# Control_Gates.net
KiCad netlist of a schematic drawn in Altium Designer
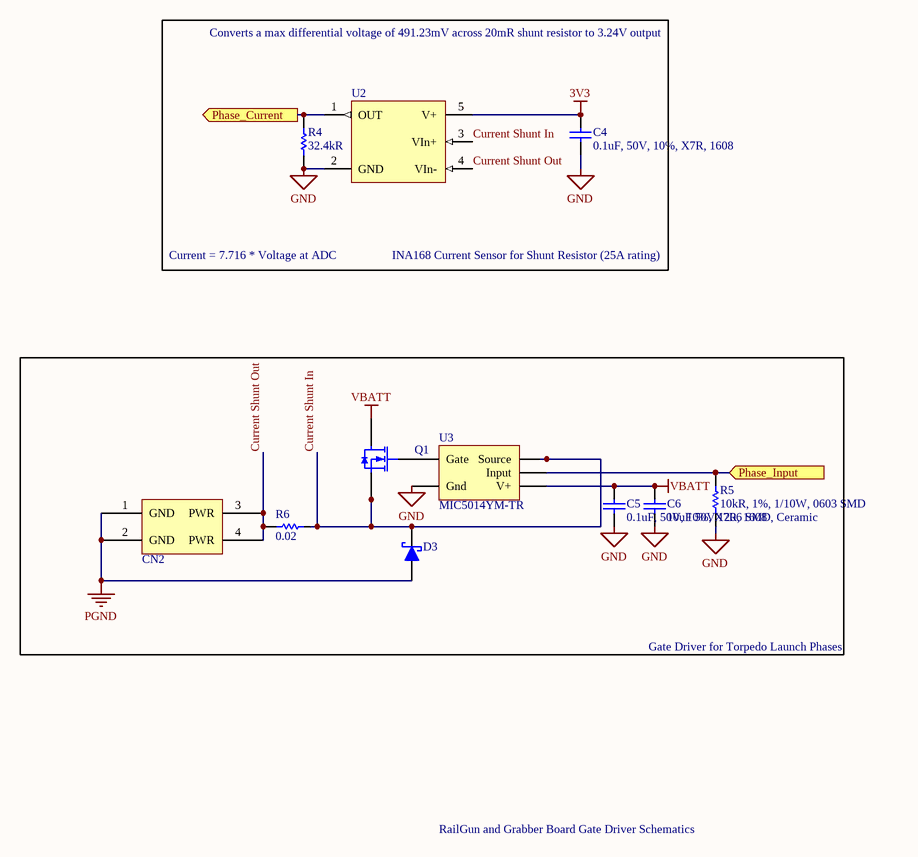
[diagram p0: Control Gates.SchDoc]

(export (version "E")
  (design (tool "Eeschema 10.0.6"))
  (components
    (comp (ref "C4")
      (value "0.1uF, 50V, 10%, X7R, 1608")
      (footprint "CAPC1608N(0603\")")
      (description "CAP CER 0.1UF 50V 10% X7R 1608 (0603)")
      (fields
        (field (name "MANUFACTURER") "Samsung Electro-Mechanics America, Inc")
        (field (name "TOLERANCE") "±10%")
      )
      (libsource (lib "AUVIC") (part "Symbol"))
    )
    (comp (ref "C5")
      (value "0.1uF, 50V, 10%, X7R, 1608")
      (footprint "CAPC1608N(0603\")")
      (description "CAP CER 0.1UF 50V 10% X7R 1608 (0603)")
      (fields
        (field (name "MANUFACTURER") "Samsung Electro-Mechanics America, Inc")
        (field (name "TOLERANCE") "±10%")
      )
      (libsource (lib "AUVIC") (part "Symbol"))
    )
    (comp (ref "C6")
      (value "10uF 50V 1206 SMD, Ceramic")
      (footprint "CAPC3216N(1206\")")
      (description "Capacitor, Ceramic, 50V, +/- 10%, 1206 SMD, X5R")
      (fields (field (name "PUBLISHER") "AUVic"))
      (libsource (lib "AUVIC") (part "Symbol"))
    )
    (comp (ref "CN2")
      (value "Header, Female, 2x2, RIght Angle, Pitch: 0.118\"  (3.00mm), THT")
      (footprint "2x2 Pitch 118mil connector")
      (description "Connector Header Through Hole, Right Angle 4 position 0.118\" (3.00mm)")
      (fields (field (name "CREATED BY") "Poorna Chander Kalidas") (field (name "PUBLISHER") "AUVic"))
      (libsource (lib "AUVIC") (part "Header, Female, 2x2, RIght Angle, Pitch{colon} 0.118{dblquote}  (3.00mm), THT"))
    )
    (comp (ref "D3")
      (value "TSSA5U50E3GCT-ND")
      (footprint "DO-214AC")
      (description "Diode Schottky 50V 5A Surface Mount DO-214AC (SMA)")
      (fields (field (name "CREATED BY") "Poorna Chander Kalidas"))
      (libsource (lib "AUVIC") (part "TSSA5U50E3GCT-ND"))
    )
    (comp (ref "Q1")
      (value "MOSFET N-Channel, 40V, 100A, 272W")
      (footprint "LFPAK-PowerSO8")
      (description "MOSFET N-Channel, 40V, 100A, 272W, Enh-Mode")
      (fields
        (field (name "MFG") "NXP Semiconductors")
        (field (name "PUBLISHER") "AUVic")
        (field (name "CREATED BY") "Ashwin Sira")
        (field (name "REVIEWED_BY") "Ashwin Sira")
      )
      (libsource (lib "AUVIC") (part "MOSFET N-Channel, 40V, 100A, 272W"))
    )
    (comp (ref "R4")
      (value "32.4kR, 1%, 0603, 1/10W")
      (footprint "RESC1609X50X30ML10T20")
      (fields (field (name "TOLERANCE") "1%") (field (name "RESISTANCE") "32.4kR"))
      (libsource (lib "AUVIC") (part "RES"))
    )
    (comp (ref "R5")
      (value "10kR, 1%, 1/10W, 0603 SMD")
      (footprint "RESC1608N(0603\")")
      (fields (field (name "MADE BY") "Ashwin Sira"))
      (libsource (lib "") (part "Symbol_1"))
    )
    (comp (ref "R6")
      (value "0.02")
      (footprint "RESC6332N(2512\")")
      (description "0R02, 1%, 2W, 2512 SMD")
      (fields (field (name "CREATED BY") "Robert Keen"))
      (libsource (lib "") (part "Symbol_1"))
    )
    (comp (ref "U2")
      (value "INA168, Current Sensor, High-Side, Analog")
      (footprint "SOT23-5")
      (fields (field (name "CREATED BY") "Jacob Lower") (field (name "PUBLISHER") "AUVic"))
      (libsource (lib "AUVIC") (part "INA168, Current Sensor, High-Side, Analog"))
    )
    (comp (ref "U3")
      (value "MIC5014YM-TR")
      (footprint "SOC 8")
      (description "High-Side or Low-Side Gate Driver IC Non-Inverting 8-SOIC")
      (libsource (lib "AUVIC") (part "Gate Driver TTL Logic 3 - 30V"))
    )
  )
  (nets
    (net (code "1") (name "/Current Shunt In") (class "Default")
      (node (ref "D3") (pin "2") (pinfunction "Cathode_2") (pintype "passive"))
      (node (ref "Q1") (pin "1") (pinfunction "Source_1") (pintype "power_in"))
      (node (ref "Q1") (pin "2") (pinfunction "Source_2") (pintype "power_in"))
      (node (ref "Q1") (pin "3") (pinfunction "Source_3") (pintype "power_in"))
      (node (ref "R6") (pin "2") (pinfunction "2_2") (pintype "passive"))
      (node (ref "U2") (pin "3") (pinfunction "VIn+_3") (pintype "input"))
      (node (ref "U3") (pin "3") (pinfunction "Source_3") (pintype "passive"))
    )
    (net (code "2") (name "/Current Shunt Out") (class "Default")
      (node (ref "CN2") (pin "3") (pinfunction "PWR_3") (pintype "passive"))
      (node (ref "CN2") (pin "4") (pinfunction "PWR_4") (pintype "passive"))
      (node (ref "R6") (pin "1") (pinfunction "1_1") (pintype "passive"))
      (node (ref "U2") (pin "4") (pinfunction "VIn-_4") (pintype "input"))
    )
    (net (code "3") (name "/Phase_Current") (class "Default")
      (node (ref "R4") (pin "2") (pinfunction "2_2") (pintype "passive"))
      (node (ref "U2") (pin "1") (pinfunction "OUT_1") (pintype "output"))
    )
    (net (code "4") (name "/Phase_Input") (class "Default")
      (node (ref "R5") (pin "1") (pinfunction "1_1") (pintype "passive"))
      (node (ref "U3") (pin "2") (pinfunction "Input_2") (pintype "passive"))
    )
    (net (code "5") (name "3V3") (class "Default")
      (node (ref "C4") (pin "2") (pinfunction "Cathode_2") (pintype "passive"))
      (node (ref "U2") (pin "5") (pinfunction "V+_5") (pintype "power_in"))
    )
    (net (code "6") (name "GND") (class "Default")
      (node (ref "C4") (pin "1") (pinfunction "Anode_1") (pintype "passive"))
      (node (ref "C5") (pin "2") (pinfunction "Cathode_2") (pintype "passive"))
      (node (ref "C6") (pin "2") (pinfunction "Cathode_2") (pintype "passive"))
      (node (ref "R4") (pin "1") (pinfunction "1_1") (pintype "passive"))
      (node (ref "R5") (pin "2") (pinfunction "2_2") (pintype "passive"))
      (node (ref "U2") (pin "2") (pinfunction "GND_2") (pintype "power_in"))
      (node (ref "U3") (pin "4") (pinfunction "Gnd_4") (pintype "passive"))
    )
    (net (code "7") (name "Net-(Q1-Gate)") (class "Default")
      (node (ref "Q1") (pin "4") (pinfunction "Gate_4") (pintype "power_in"))
      (node (ref "U3") (pin "5") (pinfunction "Gate_5") (pintype "passive"))
    )
    (net (code "8") (name "PGND") (class "Default")
      (node (ref "CN2") (pin "1") (pinfunction "GND_1") (pintype "passive"))
      (node (ref "CN2") (pin "2") (pinfunction "GND_2") (pintype "passive"))
      (node (ref "D3") (pin "1") (pinfunction "Anode_1") (pintype "passive"))
    )
    (net (code "9") (name "VBATT") (class "Default")
      (node (ref "C5") (pin "1") (pinfunction "Anode_1") (pintype "passive"))
      (node (ref "C6") (pin "1") (pinfunction "Anode_1") (pintype "passive"))
      (node (ref "Q1") (pin "5") (pinfunction "Drain_5") (pintype "power_in"))
      (node (ref "U3") (pin "1") (pinfunction "V+_1") (pintype "passive"))
    )
  )
)
